# SCH_MVS_stero_mod_2026-03-16.net
KiCad netlist of a schematic drawn in EasyEDA
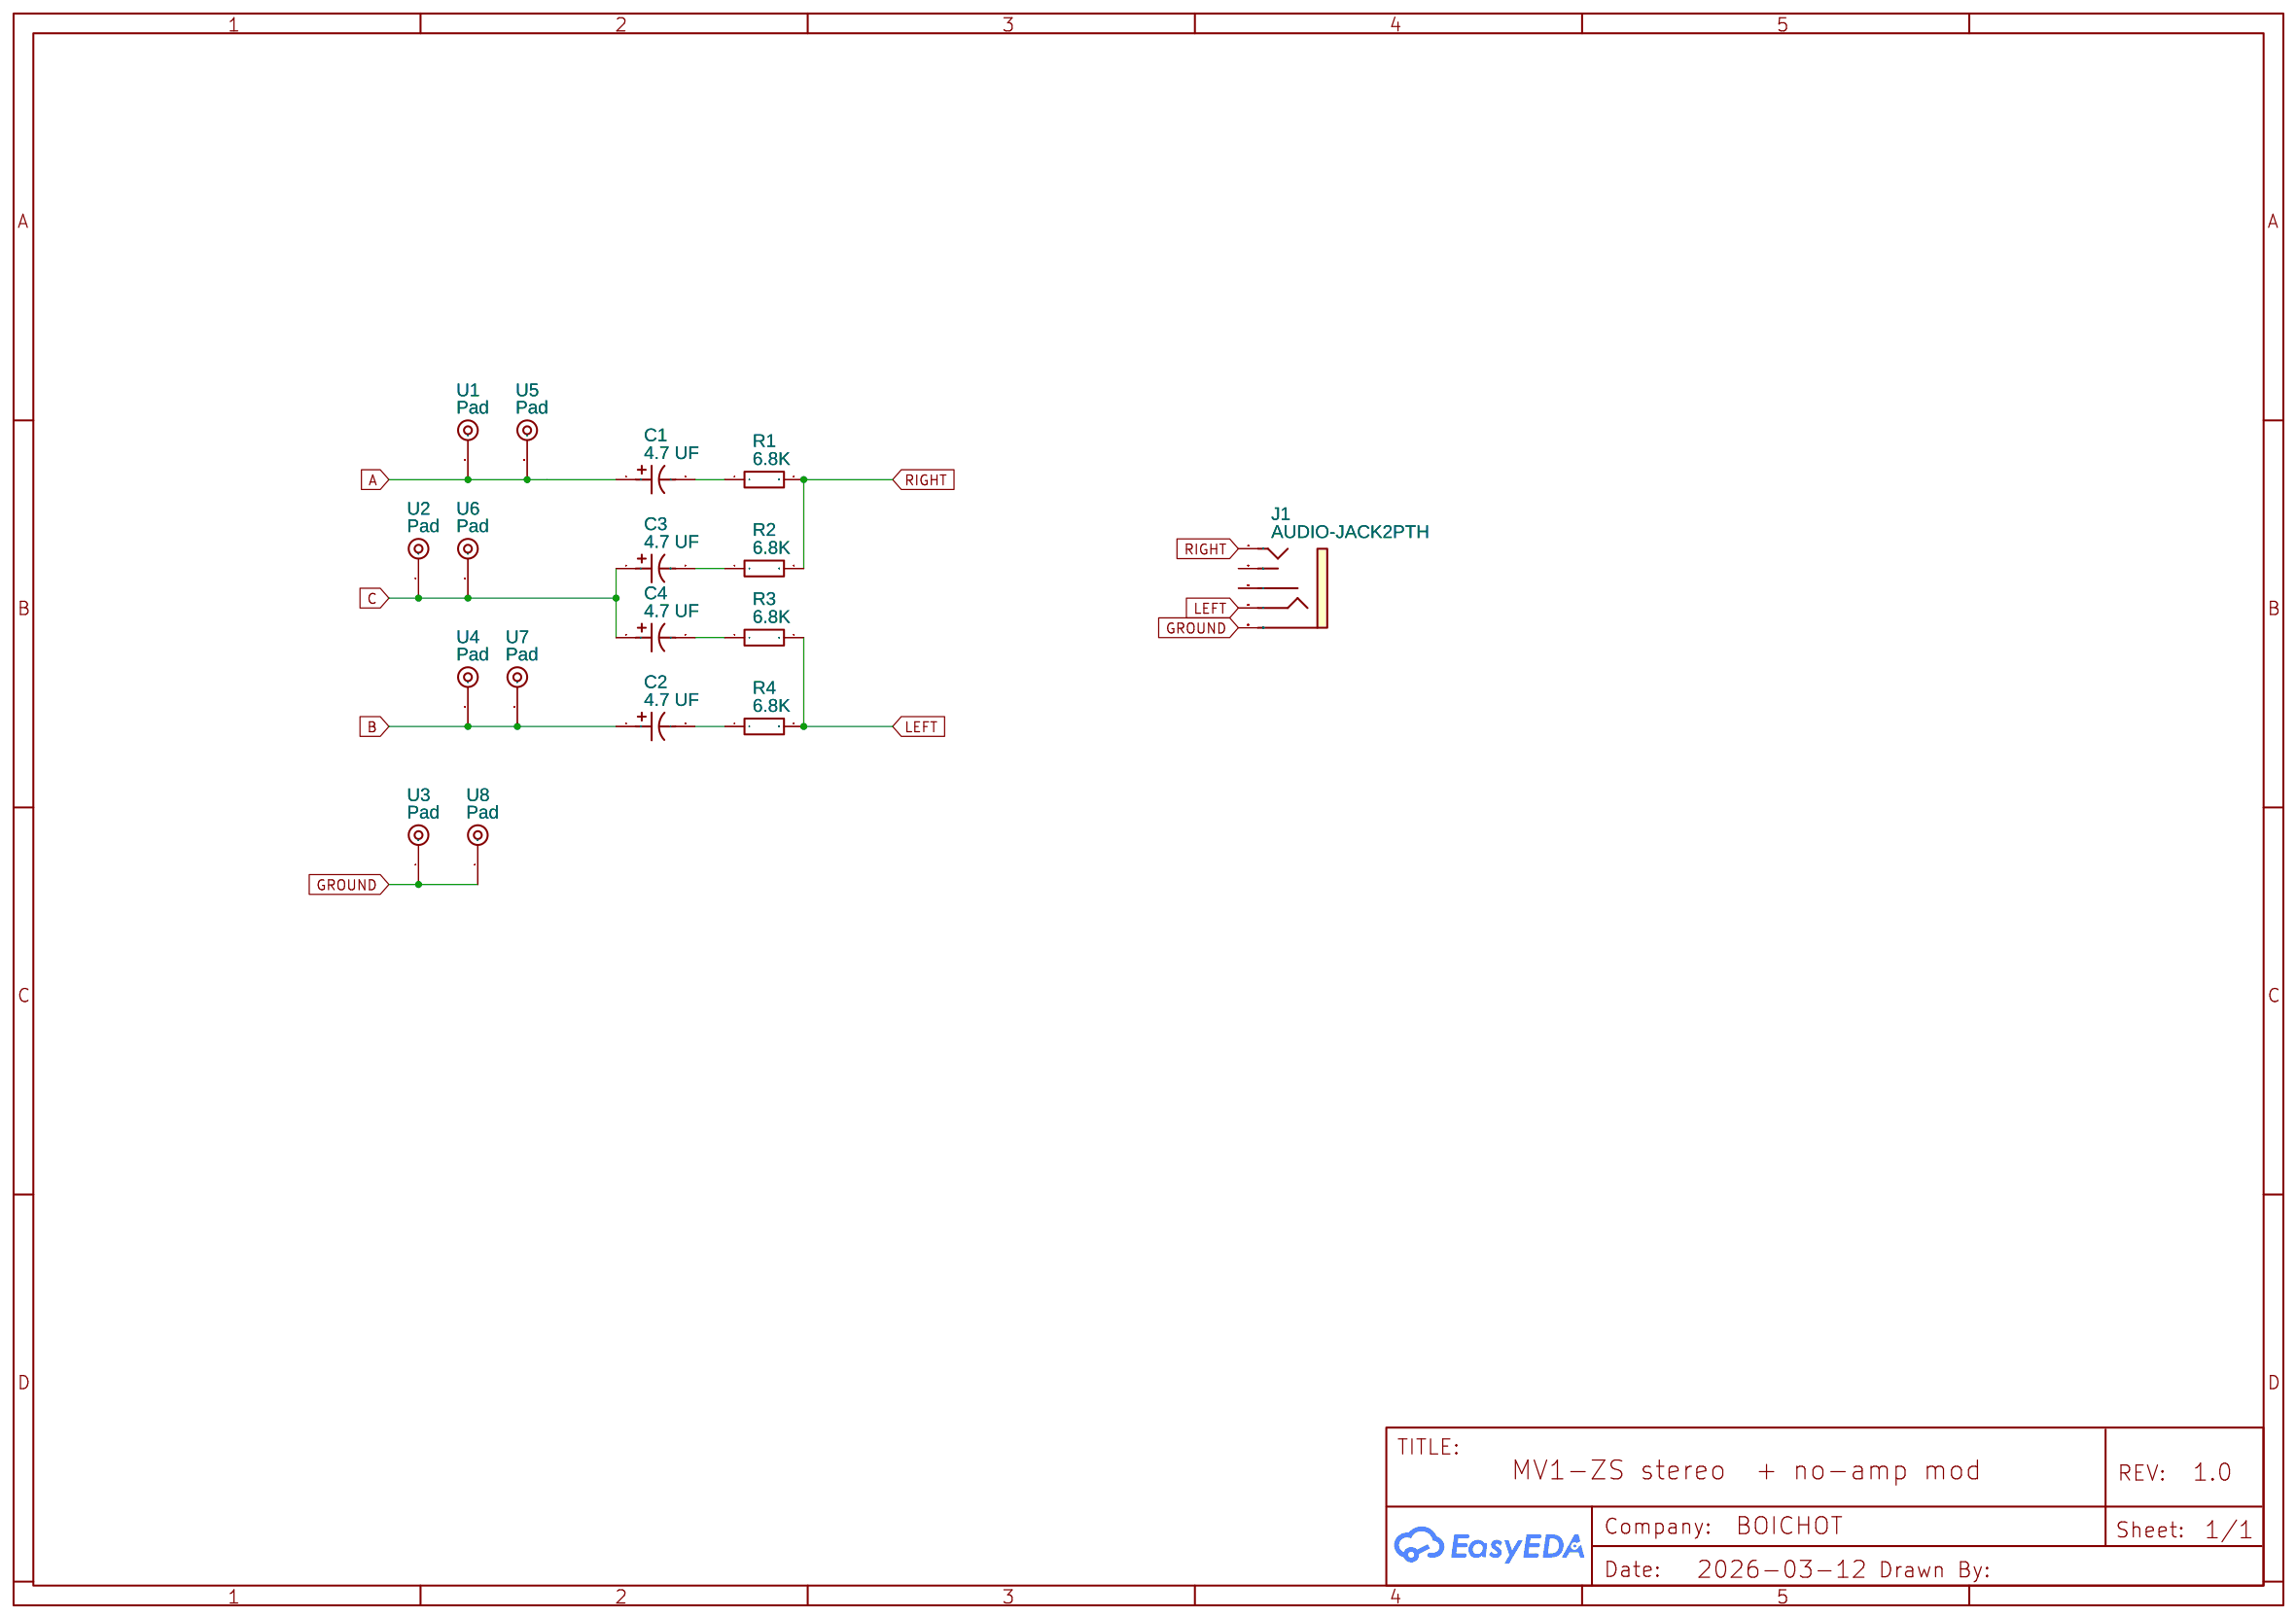
[diagram p0: schematic sheet]

(export (version "E")
  (design (tool "Eeschema 10.0.6"))
  (components
    (comp (ref "C1")
      (value "4.7 UF")
      (fields
        (field (name "Manufacturer Part") "BIPOLAR CAPACITOR 22,0 UF")
        (field (name "Manufacturer") "Visaton")
      )
      (libsource (lib "") (part "BIPOLAR CAPACITOR 22,0 UF"))
    )
    (comp (ref "C2")
      (value "4.7 UF")
      (fields
        (field (name "Manufacturer Part") "BIPOLAR CAPACITOR 22,0 UF")
        (field (name "Manufacturer") "Visaton")
      )
      (libsource (lib "") (part "BIPOLAR CAPACITOR 22,0 UF"))
    )
    (comp (ref "C3")
      (value "4.7 UF")
      (fields
        (field (name "Manufacturer Part") "BIPOLAR CAPACITOR 22,0 UF")
        (field (name "Manufacturer") "Visaton")
      )
      (libsource (lib "") (part "BIPOLAR CAPACITOR 22,0 UF"))
    )
    (comp (ref "C4")
      (value "4.7 UF")
      (fields
        (field (name "Manufacturer Part") "BIPOLAR CAPACITOR 22,0 UF")
        (field (name "Manufacturer") "Visaton")
      )
      (libsource (lib "") (part "BIPOLAR CAPACITOR 22,0 UF"))
    )
    (comp (ref "J1") (value "AUDIO-JACK2PTH") (libsource (lib "") (part "AUDIO-JACK2PTH")))
    (comp (ref "R1")
      (value "6.8K")
      (fields
        (field (name "Manufacturer Part") "EWWR0001J20R0T9")
        (field (name "Manufacturer") "ResistorToday")
      )
      (libsource (lib "") (part "RESISTOR 1/2 W"))
    )
    (comp (ref "R2")
      (value "6.8K")
      (fields
        (field (name "Manufacturer Part") "EWWR0001J20R0T9")
        (field (name "Manufacturer") "ResistorToday")
      )
      (libsource (lib "") (part "RESISTOR 1/2 W"))
    )
    (comp (ref "R3")
      (value "6.8K")
      (fields
        (field (name "Manufacturer Part") "EWWR0001J20R0T9")
        (field (name "Manufacturer") "ResistorToday")
      )
      (libsource (lib "") (part "RESISTOR 1/2 W"))
    )
    (comp (ref "R4")
      (value "6.8K")
      (fields
        (field (name "Manufacturer Part") "EWWR0001J20R0T9")
        (field (name "Manufacturer") "ResistorToday")
      )
      (libsource (lib "") (part "RESISTOR 1/2 W"))
    )
    (comp (ref "U1") (value "Pad") (libsource (lib "") (part "Connector_pad_1")))
    (comp (ref "U2") (value "Pad") (libsource (lib "") (part "Connector_pad_1")))
    (comp (ref "U3") (value "Pad") (libsource (lib "") (part "Connector_pad_1")))
    (comp (ref "U4") (value "Pad") (libsource (lib "") (part "Connector_pad_1")))
    (comp (ref "U5") (value "Pad") (libsource (lib "") (part "Connector_pad_1")))
    (comp (ref "U6") (value "Pad") (libsource (lib "") (part "Connector_pad_1")))
    (comp (ref "U7") (value "Pad") (libsource (lib "") (part "Connector_pad_1")))
    (comp (ref "U8") (value "Pad") (libsource (lib "") (part "Connector_pad_1")))
  )
  (nets
    (net (code "1") (name "A") (class "Default")
      (node (ref "C1") (pin "1") (pinfunction "1_1") (pintype "input"))
      (node (ref "U1") (pin "1") (pinfunction "1_1") (pintype "unspecified"))
      (node (ref "U5") (pin "1") (pinfunction "1_1") (pintype "unspecified"))
    )
    (net (code "2") (name "B") (class "Default")
      (node (ref "C2") (pin "1") (pinfunction "1_1") (pintype "input"))
      (node (ref "U4") (pin "1") (pinfunction "1_1") (pintype "unspecified"))
      (node (ref "U7") (pin "1") (pinfunction "1_1") (pintype "unspecified"))
    )
    (net (code "3") (name "C") (class "Default")
      (node (ref "C3") (pin "1") (pinfunction "1_1") (pintype "input"))
      (node (ref "C4") (pin "1") (pinfunction "1_1") (pintype "input"))
      (node (ref "U2") (pin "1") (pinfunction "1_1") (pintype "unspecified"))
      (node (ref "U6") (pin "1") (pinfunction "1_1") (pintype "unspecified"))
    )
    (net (code "4") (name "GROUND") (class "Default")
      (node (ref "J1") (pin "SLEEVE") (pinfunction "SLEEVE_SLEEVE") (pintype "unspecified"))
      (node (ref "U3") (pin "1") (pinfunction "1_1") (pintype "unspecified"))
      (node (ref "U8") (pin "1") (pinfunction "1_1") (pintype "unspecified"))
    )
    (net (code "5") (name "LEFT") (class "Default")
      (node (ref "J1") (pin "RING") (pinfunction "RING_RING") (pintype "unspecified"))
      (node (ref "R3") (pin "2") (pinfunction "2_2") (pintype "unspecified"))
      (node (ref "R4") (pin "2") (pinfunction "2_2") (pintype "unspecified"))
    )
    (net (code "6") (name "Net-(C1-Pad2)") (class "Default")
      (node (ref "C1") (pin "2") (pinfunction "2_2") (pintype "input"))
      (node (ref "R1") (pin "1") (pinfunction "1_1") (pintype "unspecified"))
    )
    (net (code "7") (name "Net-(C2-Pad2)") (class "Default")
      (node (ref "C2") (pin "2") (pinfunction "2_2") (pintype "input"))
      (node (ref "R4") (pin "1") (pinfunction "1_1") (pintype "unspecified"))
    )
    (net (code "8") (name "Net-(C3-Pad2)") (class "Default")
      (node (ref "C3") (pin "2") (pinfunction "2_2") (pintype "input"))
      (node (ref "R2") (pin "1") (pinfunction "1_1") (pintype "unspecified"))
    )
    (net (code "9") (name "Net-(C4-Pad2)") (class "Default")
      (node (ref "C4") (pin "2") (pinfunction "2_2") (pintype "input"))
      (node (ref "R3") (pin "1") (pinfunction "1_1") (pintype "unspecified"))
    )
    (net (code "10") (name "RIGHT") (class "Default")
      (node (ref "J1") (pin "TIP") (pinfunction "TIP_TIP") (pintype "unspecified"))
      (node (ref "R1") (pin "2") (pinfunction "2_2") (pintype "unspecified"))
      (node (ref "R2") (pin "2") (pinfunction "2_2") (pintype "unspecified"))
    )
    (net (code "11") (name "unconnected-(J1-PadRSH)") (class "Default")
      (node (ref "J1") (pin "RSH") (pinfunction "RSH_RSH") (pintype "unspecified"))
    )
    (net (code "12") (name "unconnected-(J1-PadTSH)") (class "Default")
      (node (ref "J1") (pin "TSH") (pinfunction "TSH_TSH") (pintype "unspecified"))
    )
  )
)
